# ESP.net
KiCad netlist of a schematic drawn in EAGLE
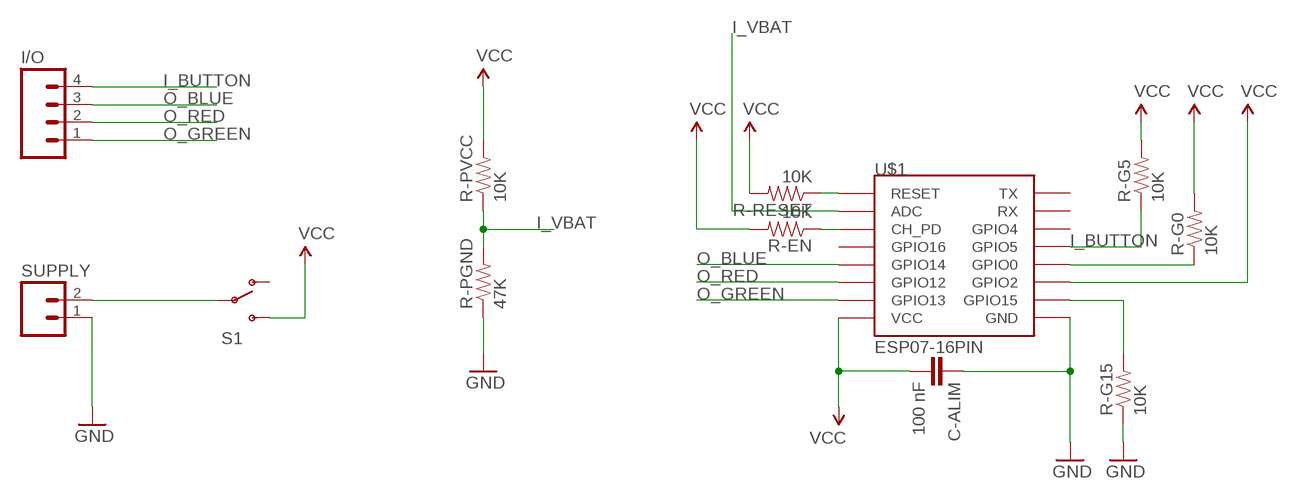
[diagram p0: schematic, sheet 1]

(export (version "E")
  (design (tool "Eeschema 10.0.6"))
  (components
    (comp (ref "C-ALIM")
      (value "100 nF")
      (footprint "eagle-import:0805")
      (libsource (lib "eagle-import") (part "CAP0805"))
    )
    (comp (ref "I/O")
      (value "M04NO_SILK_ALL_ROUND")
      (footprint "eagle-import:1X04_NO_SILK_ALL_ROUND")
      (libsource (lib "eagle-import") (part "M04NO_SILK_ALL_ROUND"))
    )
    (comp (ref "R-EN")
      (value "10K")
      (footprint "eagle-import:0805")
      (libsource (lib "eagle-import") (part "RESISTOR0805-RES"))
    )
    (comp (ref "R-G0")
      (value "10K")
      (footprint "eagle-import:0805")
      (libsource (lib "eagle-import") (part "RESISTOR0805-RES"))
    )
    (comp (ref "R-G5")
      (value "10K")
      (footprint "eagle-import:0805")
      (libsource (lib "eagle-import") (part "RESISTOR0805-RES"))
    )
    (comp (ref "R-G15")
      (value "10K")
      (footprint "eagle-import:0805")
      (libsource (lib "eagle-import") (part "RESISTOR0805-RES"))
    )
    (comp (ref "R-PGND")
      (value "47K")
      (footprint "eagle-import:0805")
      (libsource (lib "eagle-import") (part "RESISTOR0805-RES"))
    )
    (comp (ref "R-PVCC")
      (value "10K")
      (footprint "eagle-import:0805")
      (libsource (lib "eagle-import") (part "RESISTOR0805-RES"))
    )
    (comp (ref "R-RESET")
      (value "10K")
      (footprint "eagle-import:0805")
      (libsource (lib "eagle-import") (part "RESISTOR0805-RES"))
    )
    (comp (ref "S1")
      (value "SWITCH-SPDTSMD2")
      (footprint "eagle-import:SWITCH-SPDT-SMD")
      (libsource (lib "eagle-import") (part "SWITCH-SPDTSMD2"))
    )
    (comp (ref "SUPPLY")
      (value "M021X02_NO_SILK")
      (footprint "eagle-import:1X02_NO_SILK")
      (libsource (lib "eagle-import") (part "M021X02_NO_SILK"))
    )
    (comp (ref "U$1")
      (value "ESP07-16PIN")
      (footprint "eagle-import:ESP07-16PIN")
      (libsource (lib "eagle-import") (part "ESP07-16PIN"))
    )
  )
  (nets
    (net (code "1") (name "/I_BUTTON") (class "Default")
      (node (ref "I/O") (pin "4") (pinfunction "4_4") (pintype "passive"))
      (node (ref "R-G5") (pin "1") (pinfunction "1_1") (pintype "passive"))
      (node (ref "U$1") (pin "GPIO5") (pinfunction "GPIO5_GPIO5") (pintype "bidirectional"))
    )
    (net (code "2") (name "/I_VBAT") (class "Default")
      (node (ref "R-PGND") (pin "2") (pinfunction "2_2") (pintype "passive"))
      (node (ref "R-PVCC") (pin "1") (pinfunction "1_1") (pintype "passive"))
      (node (ref "U$1") (pin "ADC") (pinfunction "ADC_ADC") (pintype "bidirectional"))
    )
    (net (code "3") (name "/O_BLUE") (class "Default")
      (node (ref "I/O") (pin "3") (pinfunction "3_3") (pintype "passive"))
      (node (ref "U$1") (pin "GPIO14") (pinfunction "GPIO14_GPIO14") (pintype "bidirectional"))
    )
    (net (code "4") (name "/O_GREEN") (class "Default")
      (node (ref "I/O") (pin "1") (pinfunction "1_1") (pintype "passive"))
      (node (ref "U$1") (pin "GPIO13") (pinfunction "GPIO13_GPIO13") (pintype "bidirectional"))
    )
    (net (code "5") (name "/O_RED") (class "Default")
      (node (ref "I/O") (pin "2") (pinfunction "2_2") (pintype "passive"))
      (node (ref "U$1") (pin "GPIO12") (pinfunction "GPIO12_GPIO12") (pintype "bidirectional"))
    )
    (net (code "6") (name "GND") (class "Default")
      (node (ref "C-ALIM") (pin "1") (pinfunction "1_1") (pintype "passive"))
      (node (ref "R-G15") (pin "1") (pinfunction "1_1") (pintype "passive"))
      (node (ref "R-PGND") (pin "1") (pinfunction "1_1") (pintype "passive"))
      (node (ref "SUPPLY") (pin "1") (pinfunction "1_1") (pintype "passive"))
      (node (ref "U$1") (pin "GND") (pinfunction "GND_GND") (pintype "bidirectional"))
    )
    (net (code "7") (name "Net-(R-EN-Pad1)") (class "Default")
      (node (ref "R-EN") (pin "1") (pinfunction "1_1") (pintype "passive"))
      (node (ref "U$1") (pin "CH_PD") (pinfunction "CH_PD_CH_PD") (pintype "bidirectional"))
    )
    (net (code "8") (name "Net-(R-G0-Pad1)") (class "Default")
      (node (ref "R-G0") (pin "1") (pinfunction "1_1") (pintype "passive"))
      (node (ref "U$1") (pin "GPIO0") (pinfunction "GPIO0_GPIO0") (pintype "bidirectional"))
    )
    (net (code "9") (name "Net-(R-G15-Pad2)") (class "Default")
      (node (ref "R-G15") (pin "2") (pinfunction "2_2") (pintype "passive"))
      (node (ref "U$1") (pin "GPIO15") (pinfunction "GPIO15_GPIO15") (pintype "bidirectional"))
    )
    (net (code "10") (name "Net-(S1-P)") (class "Default")
      (node (ref "S1") (pin "2") (pinfunction "P_2") (pintype "passive"))
      (node (ref "SUPPLY") (pin "2") (pinfunction "2_2") (pintype "passive"))
    )
    (net (code "11") (name "Net-(U$1-RESET)") (class "Default")
      (node (ref "R-RESET") (pin "1") (pinfunction "1_1") (pintype "passive"))
      (node (ref "U$1") (pin "REST") (pinfunction "RESET_REST") (pintype "bidirectional"))
    )
    (net (code "12") (name "VCC") (class "Default")
      (node (ref "C-ALIM") (pin "2") (pinfunction "2_2") (pintype "passive"))
      (node (ref "R-EN") (pin "2") (pinfunction "2_2") (pintype "passive"))
      (node (ref "R-G0") (pin "2") (pinfunction "2_2") (pintype "passive"))
      (node (ref "R-G5") (pin "2") (pinfunction "2_2") (pintype "passive"))
      (node (ref "R-PVCC") (pin "2") (pinfunction "2_2") (pintype "passive"))
      (node (ref "R-RESET") (pin "2") (pinfunction "2_2") (pintype "passive"))
      (node (ref "S1") (pin "3") (pinfunction "S_3") (pintype "passive"))
      (node (ref "U$1") (pin "GPIO2") (pinfunction "GPIO2_GPIO2") (pintype "bidirectional"))
      (node (ref "U$1") (pin "VCC") (pinfunction "VCC_VCC") (pintype "bidirectional"))
    )
    (net (code "13") (name "unconnected-(S1-O-Pad1)") (class "Default")
      (node (ref "S1") (pin "1") (pinfunction "O_1") (pintype "passive"))
    )
    (net (code "14") (name "unconnected-(U$1-PadGPIO4)") (class "Default")
      (node (ref "U$1") (pin "GPIO4") (pinfunction "GPIO4_GPIO4") (pintype "bidirectional"))
    )
    (net (code "15") (name "unconnected-(U$1-PadGPIO16)") (class "Default")
      (node (ref "U$1") (pin "GPIO16") (pinfunction "GPIO16_GPIO16") (pintype "bidirectional"))
    )
    (net (code "16") (name "unconnected-(U$1-PadRX)") (class "Default")
      (node (ref "U$1") (pin "RX") (pinfunction "RX_RX") (pintype "bidirectional"))
    )
    (net (code "17") (name "unconnected-(U$1-PadTX)") (class "Default")
      (node (ref "U$1") (pin "TX") (pinfunction "TX_TX") (pintype "bidirectional"))
    )
  )
)
